# Sheet1.net
KiCad netlist of a schematic drawn in Altium Designer
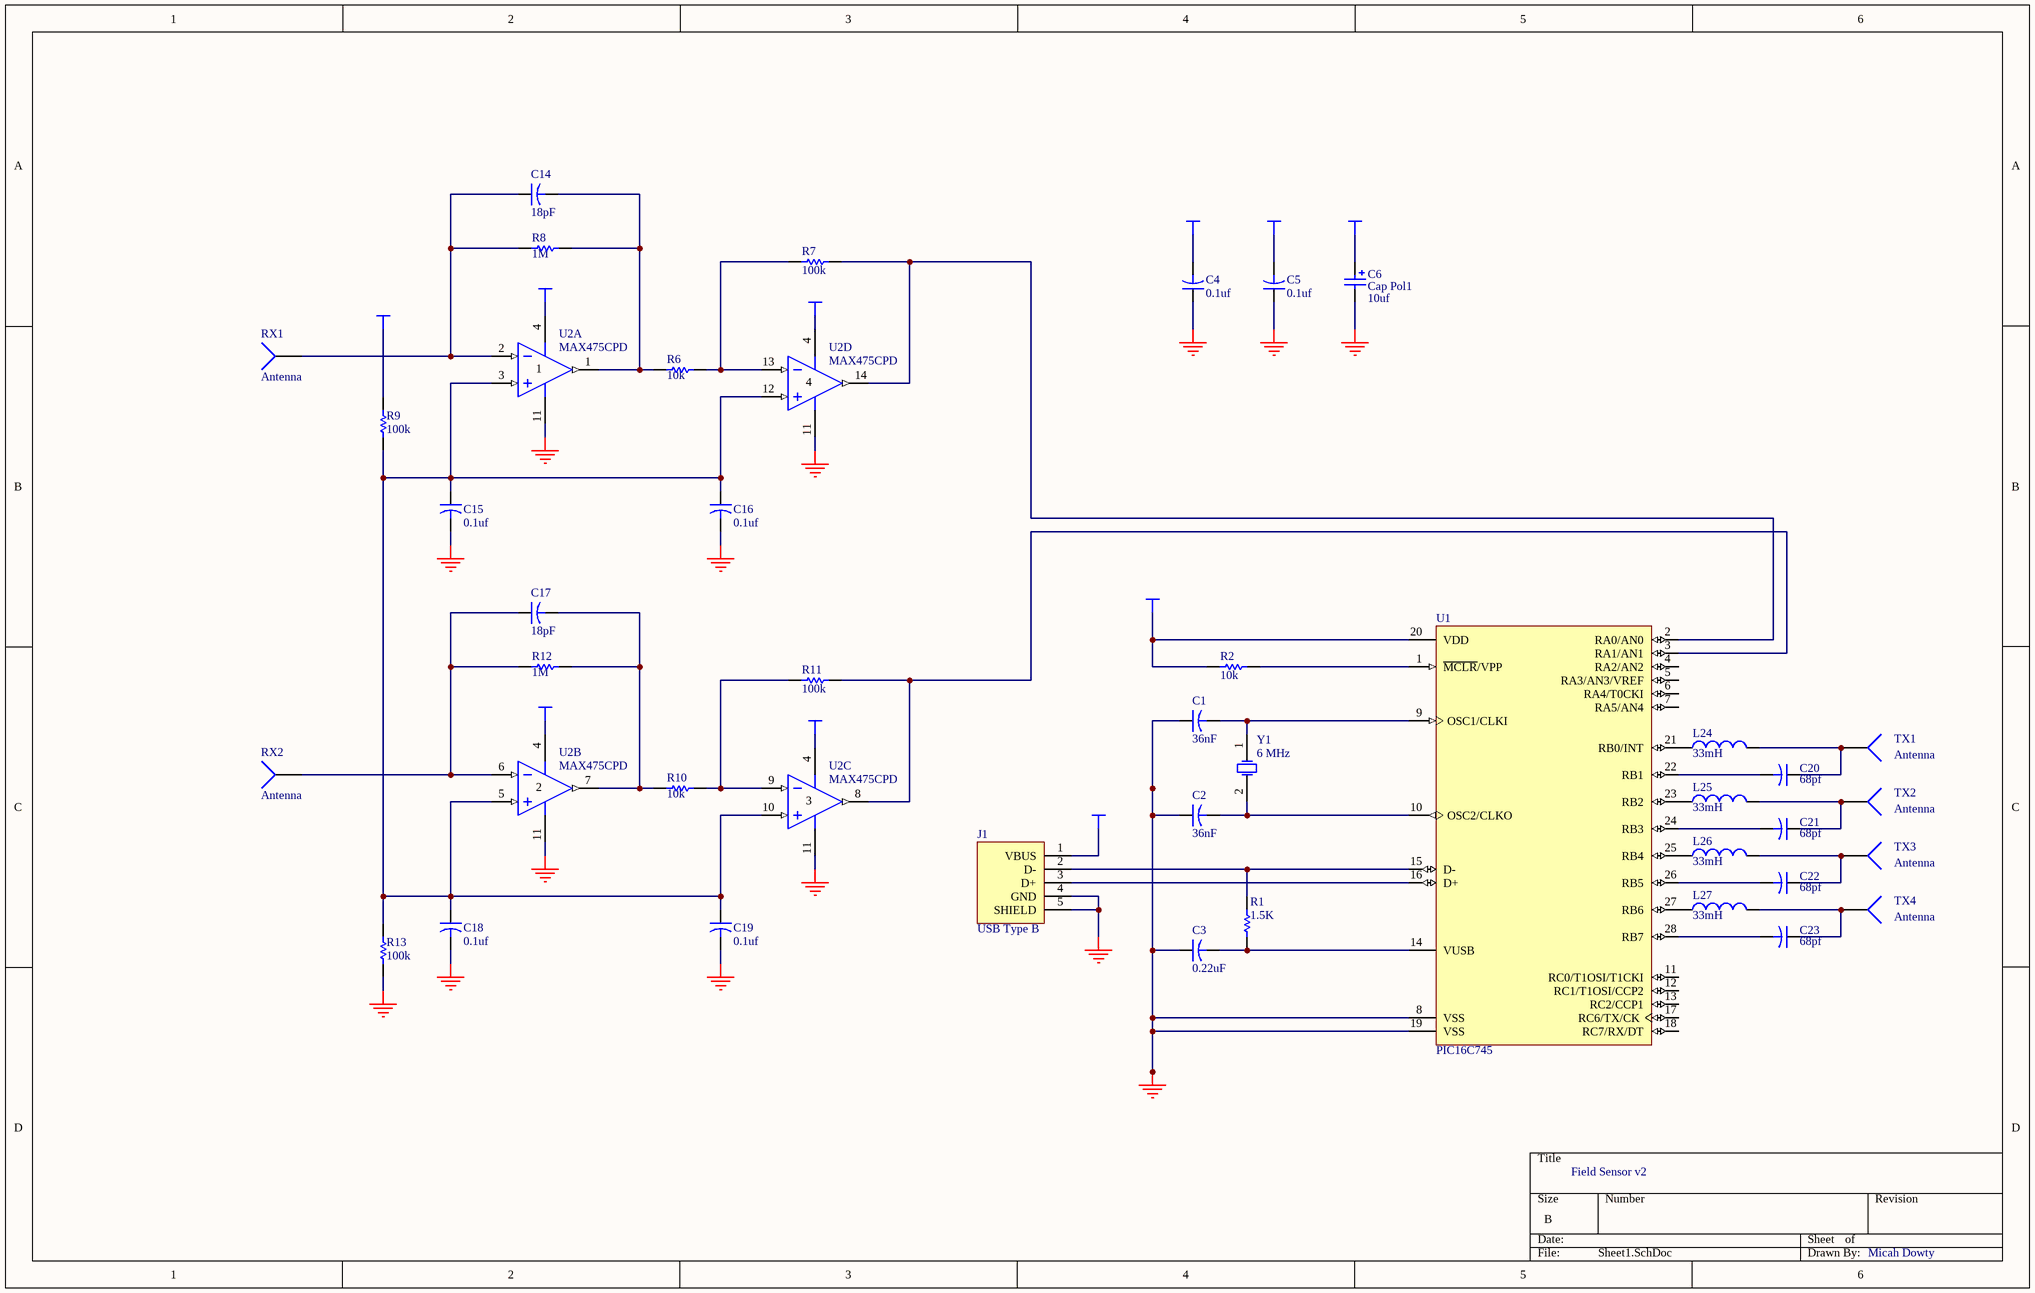
[diagram p0: Sheet1.SchDoc]

(export (version "E")
  (design (tool "Eeschema 10.0.6"))
  (components
    (comp (ref "C1")
      (value "Cap2")
      (footprint "CAPR5-4X5")
      (description "Capacitor")
      (fields
        (field (name "MANUFACTURER") "Generic Components")
        (field (name "ALTIUM_VALUE") "36nF")
        (field (name "PUBLISHER") "Altium Limited")
      )
      (libsource (lib "Miscellaneous Devices") (part "Cap2"))
    )
    (comp (ref "C2")
      (value "Cap2")
      (footprint "CAPR5-4X5")
      (description "Capacitor")
      (fields
        (field (name "MANUFACTURER") "Generic Components")
        (field (name "ALTIUM_VALUE") "36nF")
        (field (name "PUBLISHER") "Altium Limited")
      )
      (libsource (lib "Miscellaneous Devices") (part "Cap2"))
    )
    (comp (ref "C3")
      (value "0.22uF")
      (footprint "CAPR5-4X5")
      (description "Capacitor")
      (fields (field (name "MANUFACTURER") "Generic Components") (field (name "PUBLISHER") "Altium Limited"))
      (libsource (lib "Miscellaneous Devices") (part "Cap2"))
    )
    (comp (ref "C4")
      (value "0.1uf")
      (footprint "CAPR5-4X5")
      (description "Capacitor")
      (fields (field (name "MANUFACTURER") "Generic Components") (field (name "PUBLISHER") "Altium Limited"))
      (libsource (lib "Miscellaneous Devices") (part "Cap2"))
    )
    (comp (ref "C5")
      (value "0.1uf")
      (footprint "CAPR5-4X5")
      (description "Capacitor")
      (fields (field (name "MANUFACTURER") "Generic Components") (field (name "PUBLISHER") "Altium Limited"))
      (libsource (lib "Miscellaneous Devices") (part "Cap2"))
    )
    (comp (ref "C6")
      (value "Cap Pol1")
      (footprint "CAP-EE-1")
      (description "Polarized Capacitor (Radial)")
      (fields
        (field (name "MANUFACTURER") "Generic Components")
        (field (name "ALTIUM_VALUE") "10uf")
        (field (name "PUBLISHER") "Altium Limited")
      )
      (libsource (lib "Miscellaneous Devices") (part "Cap Pol1"))
    )
    (comp (ref "C14")
      (value "Cap2")
      (footprint "CAPR5-4X5")
      (description "Capacitor")
      (fields
        (field (name "MANUFACTURER") "Generic Components")
        (field (name "ALTIUM_VALUE") "18pF")
        (field (name "PUBLISHER") "Altium Limited")
      )
      (libsource (lib "Miscellaneous Devices") (part "Cap2"))
    )
    (comp (ref "C15")
      (value "Cap2")
      (footprint "CAPR5-4X5")
      (description "Capacitor")
      (fields
        (field (name "MANUFACTURER") "Generic Components")
        (field (name "ALTIUM_VALUE") "0.1uf")
        (field (name "PUBLISHER") "Altium Limited")
      )
      (libsource (lib "Miscellaneous Devices") (part "Cap2"))
    )
    (comp (ref "C16")
      (value "Cap2")
      (footprint "CAPR5-4X5")
      (description "Capacitor")
      (fields
        (field (name "MANUFACTURER") "Generic Components")
        (field (name "ALTIUM_VALUE") "0.1uf")
        (field (name "PUBLISHER") "Altium Limited")
      )
      (libsource (lib "Miscellaneous Devices") (part "Cap2"))
    )
    (comp (ref "C17")
      (value "Cap2")
      (footprint "CAPR5-4X5")
      (description "Capacitor")
      (fields
        (field (name "MANUFACTURER") "Generic Components")
        (field (name "ALTIUM_VALUE") "18pF")
        (field (name "PUBLISHER") "Altium Limited")
      )
      (libsource (lib "Miscellaneous Devices") (part "Cap2"))
    )
    (comp (ref "C18")
      (value "Cap2")
      (footprint "CAPR5-4X5")
      (description "Capacitor")
      (fields
        (field (name "MANUFACTURER") "Generic Components")
        (field (name "ALTIUM_VALUE") "0.1uf")
        (field (name "PUBLISHER") "Altium Limited")
      )
      (libsource (lib "Miscellaneous Devices") (part "Cap2"))
    )
    (comp (ref "C19")
      (value "Cap2")
      (footprint "CAPR5-4X5")
      (description "Capacitor")
      (fields
        (field (name "MANUFACTURER") "Generic Components")
        (field (name "ALTIUM_VALUE") "0.1uf")
        (field (name "PUBLISHER") "Altium Limited")
      )
      (libsource (lib "Miscellaneous Devices") (part "Cap2"))
    )
    (comp (ref "C20")
      (value "Cap2")
      (footprint "CAPR5-4X5")
      (description "Capacitor")
      (fields
        (field (name "MANUFACTURER") "Generic Components")
        (field (name "ALTIUM_VALUE") "68pf")
        (field (name "PUBLISHER") "Altium Limited")
      )
      (libsource (lib "Miscellaneous Devices") (part "Cap2"))
    )
    (comp (ref "C21")
      (value "Cap2")
      (footprint "CAPR5-4X5")
      (description "Capacitor")
      (fields
        (field (name "MANUFACTURER") "Generic Components")
        (field (name "ALTIUM_VALUE") "68pf")
        (field (name "PUBLISHER") "Altium Limited")
      )
      (libsource (lib "Miscellaneous Devices") (part "Cap2"))
    )
    (comp (ref "C22")
      (value "Cap2")
      (footprint "CAPR5-4X5")
      (description "Capacitor")
      (fields
        (field (name "MANUFACTURER") "Generic Components")
        (field (name "ALTIUM_VALUE") "68pf")
        (field (name "PUBLISHER") "Altium Limited")
      )
      (libsource (lib "Miscellaneous Devices") (part "Cap2"))
    )
    (comp (ref "C23")
      (value "Cap2")
      (footprint "CAPR5-4X5")
      (description "Capacitor")
      (fields
        (field (name "MANUFACTURER") "Generic Components")
        (field (name "ALTIUM_VALUE") "68pf")
        (field (name "PUBLISHER") "Altium Limited")
      )
      (libsource (lib "Miscellaneous Devices") (part "Cap2"))
    )
    (comp (ref "J1")
      (value "USB")
      (footprint "USB-TYPEB")
      (description "Header, 4-Pin")
      (fields (field (name "MANUFACTURER") "Generic Components") (field (name "PUBLISHER") "Altium Limited"))
      (libsource (lib "parts") (part "USB Type B"))
    )
    (comp (ref "L24")
      (value "33mH")
      (footprint "RAD-0.2")
      (description "Inductor")
      (fields (field (name "MANUFACTURER") "Generic Components") (field (name "PUBLISHER") "Altium Limited"))
      (libsource (lib "Miscellaneous Devices") (part "Inductor"))
    )
    (comp (ref "L25")
      (value "33mH")
      (footprint "RAD-0.2")
      (description "Inductor")
      (fields (field (name "MANUFACTURER") "Generic Components") (field (name "PUBLISHER") "Altium Limited"))
      (libsource (lib "Miscellaneous Devices") (part "Inductor"))
    )
    (comp (ref "L26")
      (value "33mH")
      (footprint "RAD-0.2")
      (description "Inductor")
      (fields (field (name "MANUFACTURER") "Generic Components") (field (name "PUBLISHER") "Altium Limited"))
      (libsource (lib "Miscellaneous Devices") (part "Inductor"))
    )
    (comp (ref "L27")
      (value "33mH")
      (footprint "RAD-0.2")
      (description "Inductor")
      (fields (field (name "MANUFACTURER") "Generic Components") (field (name "PUBLISHER") "Altium Limited"))
      (libsource (lib "Miscellaneous Devices") (part "Inductor"))
    )
    (comp (ref "R1")
      (value "Res1")
      (footprint "AXIAL-0.3")
      (description "Resistor")
      (fields
        (field (name "MANUFACTURER") "Generic Components")
        (field (name "ALTIUM_VALUE") "1.5K")
        (field (name "PUBLISHER") "Altium Limited")
      )
      (libsource (lib "Miscellaneous Devices") (part "Res1"))
    )
    (comp (ref "R2")
      (value "Res1")
      (footprint "AXIAL-0.3")
      (description "Resistor")
      (fields
        (field (name "MANUFACTURER") "Generic Components")
        (field (name "ALTIUM_VALUE") "10k")
        (field (name "PUBLISHER") "Altium Limited")
      )
      (libsource (lib "Miscellaneous Devices") (part "Res1"))
    )
    (comp (ref "R6")
      (value "Res1")
      (footprint "AXIAL-0.3")
      (description "Resistor")
      (fields
        (field (name "MANUFACTURER") "Generic Components")
        (field (name "ALTIUM_VALUE") "10k")
        (field (name "PUBLISHER") "Altium Limited")
      )
      (libsource (lib "Miscellaneous Devices") (part "Res1"))
    )
    (comp (ref "R7")
      (value "Res1")
      (footprint "AXIAL-0.3")
      (description "Resistor")
      (fields
        (field (name "MANUFACTURER") "Generic Components")
        (field (name "ALTIUM_VALUE") "100k")
        (field (name "PUBLISHER") "Altium Limited")
      )
      (libsource (lib "Miscellaneous Devices") (part "Res1"))
    )
    (comp (ref "R8")
      (value "Res1")
      (footprint "AXIAL-0.3")
      (description "Resistor")
      (fields
        (field (name "MANUFACTURER") "Generic Components")
        (field (name "ALTIUM_VALUE") "1M")
        (field (name "PUBLISHER") "Altium Limited")
      )
      (libsource (lib "Miscellaneous Devices") (part "Res1"))
    )
    (comp (ref "R9")
      (value "Res1")
      (footprint "AXIAL-0.3")
      (description "Resistor")
      (fields
        (field (name "MANUFACTURER") "Generic Components")
        (field (name "ALTIUM_VALUE") "100k")
        (field (name "PUBLISHER") "Altium Limited")
      )
      (libsource (lib "Miscellaneous Devices") (part "Res1"))
    )
    (comp (ref "R10")
      (value "Res1")
      (footprint "AXIAL-0.3")
      (description "Resistor")
      (fields
        (field (name "MANUFACTURER") "Generic Components")
        (field (name "ALTIUM_VALUE") "10k")
        (field (name "PUBLISHER") "Altium Limited")
      )
      (libsource (lib "Miscellaneous Devices") (part "Res1"))
    )
    (comp (ref "R11")
      (value "Res1")
      (footprint "AXIAL-0.3")
      (description "Resistor")
      (fields
        (field (name "MANUFACTURER") "Generic Components")
        (field (name "ALTIUM_VALUE") "100k")
        (field (name "PUBLISHER") "Altium Limited")
      )
      (libsource (lib "Miscellaneous Devices") (part "Res1"))
    )
    (comp (ref "R12")
      (value "Res1")
      (footprint "AXIAL-0.3")
      (description "Resistor")
      (fields
        (field (name "MANUFACTURER") "Generic Components")
        (field (name "ALTIUM_VALUE") "1M")
        (field (name "PUBLISHER") "Altium Limited")
      )
      (libsource (lib "Miscellaneous Devices") (part "Res1"))
    )
    (comp (ref "R13")
      (value "Res1")
      (footprint "AXIAL-0.3")
      (description "Resistor")
      (fields
        (field (name "MANUFACTURER") "Generic Components")
        (field (name "ALTIUM_VALUE") "100k")
        (field (name "PUBLISHER") "Altium Limited")
      )
      (libsource (lib "Miscellaneous Devices") (part "Res1"))
    )
    (comp (ref "RX1")
      (value "Antenna")
      (footprint "FIELD_ANTENNA")
      (description "Socket")
      (fields (field (name "MANUFACTURER") "Generic Components") (field (name "PUBLISHER") "Altium Limited"))
      (libsource (lib "Miscellaneous Connectors") (part "Socket"))
    )
    (comp (ref "RX2")
      (value "Antenna")
      (footprint "FIELD_ANTENNA")
      (description "Socket")
      (fields (field (name "MANUFACTURER") "Generic Components") (field (name "PUBLISHER") "Altium Limited"))
      (libsource (lib "Miscellaneous Connectors") (part "Socket"))
    )
    (comp (ref "TX1")
      (value "Antenna")
      (footprint "FIELD_ANTENNA")
      (description "Socket")
      (fields (field (name "MANUFACTURER") "Generic Components") (field (name "PUBLISHER") "Altium Limited"))
      (libsource (lib "Miscellaneous Connectors") (part "Socket"))
    )
    (comp (ref "TX2")
      (value "Antenna")
      (footprint "FIELD_ANTENNA")
      (description "Socket")
      (fields (field (name "MANUFACTURER") "Generic Components") (field (name "PUBLISHER") "Altium Limited"))
      (libsource (lib "Miscellaneous Connectors") (part "Socket"))
    )
    (comp (ref "TX3")
      (value "Antenna")
      (footprint "FIELD_ANTENNA")
      (description "Socket")
      (fields (field (name "MANUFACTURER") "Generic Components") (field (name "PUBLISHER") "Altium Limited"))
      (libsource (lib "Miscellaneous Connectors") (part "Socket"))
    )
    (comp (ref "TX4")
      (value "Antenna")
      (footprint "FIELD_ANTENNA")
      (description "Socket")
      (fields (field (name "MANUFACTURER") "Generic Components") (field (name "PUBLISHER") "Altium Limited"))
      (libsource (lib "Miscellaneous Connectors") (part "Socket"))
    )
    (comp (ref "U1")
      (value "~")
      (footprint "DIP-28")
      (description "EPROM-Based 8-Bit CMOS Microcontroller with USB")
      (fields (field (name "MANUFACTURER") "Microchip"))
      (libsource (lib "parts") (part "PIC16C745"))
    )
    (comp (ref "U2")
      (value "MAX475CPD")
      (footprint "DIP-14/D19.7")
      (description "Quad 10MHz, Single Supply Operational Amplifier")
      (fields (field (name "MANUFACTURER") "Maxim") (field (name "PUBLISHER") "Altium Limited"))
      (libsource (lib "Maxim Operational Amplifier") (part "MAX475CPD"))
    )
    (comp (ref "Y1")
      (value "6 MHz")
      (footprint "BCY-W2/E4.7")
      (description "Crystal Oscillator")
      (fields (field (name "MANUFACTURER") "Generic Components") (field (name "PUBLISHER") "Altium Limited"))
      (libsource (lib "Miscellaneous Devices") (part "XTAL"))
    )
  )
  (nets
    (net (code "1") (name "GND") (class "Default")
      (node (ref "C1") (pin "1") (pinfunction "1_1") (pintype "passive"))
      (node (ref "C15") (pin "2") (pinfunction "2_2") (pintype "passive"))
      (node (ref "C16") (pin "2") (pinfunction "2_2") (pintype "passive"))
      (node (ref "C18") (pin "2") (pinfunction "2_2") (pintype "passive"))
      (node (ref "C19") (pin "2") (pinfunction "2_2") (pintype "passive"))
      (node (ref "C2") (pin "1") (pinfunction "1_1") (pintype "passive"))
      (node (ref "C3") (pin "1") (pinfunction "1_1") (pintype "passive"))
      (node (ref "C4") (pin "1") (pinfunction "1_1") (pintype "passive"))
      (node (ref "C5") (pin "1") (pinfunction "1_1") (pintype "passive"))
      (node (ref "C6") (pin "2") (pinfunction "2_2") (pintype "passive"))
      (node (ref "J1") (pin "4") (pinfunction "GND_4") (pintype "passive"))
      (node (ref "J1") (pin "5") (pinfunction "SHIELD_5") (pintype "power_in"))
      (node (ref "R13") (pin "1") (pinfunction "1_1") (pintype "passive"))
      (node (ref "U1") (pin "19") (pinfunction "VSS_19") (pintype "power_in"))
      (node (ref "U1") (pin "8") (pinfunction "VSS_8") (pintype "power_in"))
      (node (ref "U2") (pin "11") (pinfunction "VEE_11") (pintype "power_in"))
    )
    (net (code "2") (name "Net-(C20-Pad1)") (class "Default")
      (node (ref "C20") (pin "1") (pinfunction "1_1") (pintype "passive"))
      (node (ref "L24") (pin "2") (pinfunction "2_2") (pintype "passive"))
      (node (ref "TX1") (pin "1") (pinfunction "1_1") (pintype "passive"))
    )
    (net (code "3") (name "Net-(C21-Pad1)") (class "Default")
      (node (ref "C21") (pin "1") (pinfunction "1_1") (pintype "passive"))
      (node (ref "L25") (pin "2") (pinfunction "2_2") (pintype "passive"))
      (node (ref "TX2") (pin "1") (pinfunction "1_1") (pintype "passive"))
    )
    (net (code "4") (name "Net-(C22-Pad1)") (class "Default")
      (node (ref "C22") (pin "1") (pinfunction "1_1") (pintype "passive"))
      (node (ref "L26") (pin "2") (pinfunction "2_2") (pintype "passive"))
      (node (ref "TX3") (pin "1") (pinfunction "1_1") (pintype "passive"))
    )
    (net (code "5") (name "Net-(C23-Pad1)") (class "Default")
      (node (ref "C23") (pin "1") (pinfunction "1_1") (pintype "passive"))
      (node (ref "L27") (pin "2") (pinfunction "2_2") (pintype "passive"))
      (node (ref "TX4") (pin "1") (pinfunction "1_1") (pintype "passive"))
    )
    (net (code "6") (name "Net-(J1-D+)") (class "Default")
      (node (ref "J1") (pin "3") (pinfunction "D+_3") (pintype "passive"))
      (node (ref "U1") (pin "16") (pinfunction "D+_16") (pintype "bidirectional"))
    )
    (net (code "7") (name "Net-(J1-D-)") (class "Default")
      (node (ref "J1") (pin "2") (pinfunction "D-_2") (pintype "passive"))
      (node (ref "R1") (pin "2") (pinfunction "2_2") (pintype "passive"))
      (node (ref "U1") (pin "15") (pinfunction "D-_15") (pintype "bidirectional"))
    )
    (net (code "8") (name "Net-(U1-OSC1{slash}CLKI)") (class "Default")
      (node (ref "C1") (pin "2") (pinfunction "2_2") (pintype "passive"))
      (node (ref "U1") (pin "9") (pinfunction "OSC1/CLKI_9") (pintype "input"))
      (node (ref "Y1") (pin "1") (pinfunction "OSC1_1") (pintype "passive"))
    )
    (net (code "9") (name "Net-(U1-OSC2{slash}CLKO)") (class "Default")
      (node (ref "C2") (pin "2") (pinfunction "2_2") (pintype "passive"))
      (node (ref "U1") (pin "10") (pinfunction "OSC2/CLKO_10") (pintype "output"))
      (node (ref "Y1") (pin "2") (pinfunction "OSC2_2") (pintype "passive"))
    )
    (net (code "10") (name "Net-(U1-RA0{slash}AN0)") (class "Default")
      (node (ref "R7") (pin "2") (pinfunction "2_2") (pintype "passive"))
      (node (ref "U1") (pin "2") (pinfunction "RA0/AN0_2") (pintype "bidirectional"))
      (node (ref "U2") (pin "14") (pinfunction "OUT_14") (pintype "output"))
    )
    (net (code "11") (name "Net-(U1-RA1{slash}AN1)") (class "Default")
      (node (ref "R11") (pin "2") (pinfunction "2_2") (pintype "passive"))
      (node (ref "U1") (pin "3") (pinfunction "RA1/AN1_3") (pintype "bidirectional"))
      (node (ref "U2") (pin "8") (pinfunction "OUT_8") (pintype "output"))
    )
    (net (code "12") (name "Net-(U1-RB0{slash}INT)") (class "Default")
      (node (ref "L24") (pin "1") (pinfunction "1_1") (pintype "passive"))
      (node (ref "U1") (pin "21") (pinfunction "RB0/INT_21") (pintype "bidirectional"))
    )
    (net (code "13") (name "Net-(U1-RB1)") (class "Default")
      (node (ref "C20") (pin "2") (pinfunction "2_2") (pintype "passive"))
      (node (ref "U1") (pin "22") (pinfunction "RB1_22") (pintype "bidirectional"))
    )
    (net (code "14") (name "Net-(U1-RB2)") (class "Default")
      (node (ref "L25") (pin "1") (pinfunction "1_1") (pintype "passive"))
      (node (ref "U1") (pin "23") (pinfunction "RB2_23") (pintype "bidirectional"))
    )
    (net (code "15") (name "Net-(U1-RB3)") (class "Default")
      (node (ref "C21") (pin "2") (pinfunction "2_2") (pintype "passive"))
      (node (ref "U1") (pin "24") (pinfunction "RB3_24") (pintype "bidirectional"))
    )
    (net (code "16") (name "Net-(U1-RB4)") (class "Default")
      (node (ref "L26") (pin "1") (pinfunction "1_1") (pintype "passive"))
      (node (ref "U1") (pin "25") (pinfunction "RB4_25") (pintype "bidirectional"))
    )
    (net (code "17") (name "Net-(U1-RB5)") (class "Default")
      (node (ref "C22") (pin "2") (pinfunction "2_2") (pintype "passive"))
      (node (ref "U1") (pin "26") (pinfunction "RB5_26") (pintype "bidirectional"))
    )
    (net (code "18") (name "Net-(U1-RB6)") (class "Default")
      (node (ref "L27") (pin "1") (pinfunction "1_1") (pintype "passive"))
      (node (ref "U1") (pin "27") (pinfunction "RB6_27") (pintype "bidirectional"))
    )
    (net (code "19") (name "Net-(U1-RB7)") (class "Default")
      (node (ref "C23") (pin "2") (pinfunction "2_2") (pintype "passive"))
      (node (ref "U1") (pin "28") (pinfunction "RB7_28") (pintype "bidirectional"))
    )
    (net (code "20") (name "Net-(U1-VUSB)") (class "Default")
      (node (ref "C3") (pin "2") (pinfunction "2_2") (pintype "passive"))
      (node (ref "R1") (pin "1") (pinfunction "1_1") (pintype "passive"))
      (node (ref "U1") (pin "14") (pinfunction "VUSB_14") (pintype "power_in"))
    )
    (net (code "21") (name "Net-(U1-~{MCLR}{slash}VPP)") (class "Default")
      (node (ref "R2") (pin "1") (pinfunction "1_1") (pintype "passive"))
      (node (ref "U1") (pin "1") (pinfunction "~{MCLR}/VPP_1") (pintype "input"))
    )
    (net (code "22") (name "Net-(U2A-IN+)") (class "Default")
      (node (ref "C15") (pin "1") (pinfunction "1_1") (pintype "passive"))
      (node (ref "C16") (pin "1") (pinfunction "1_1") (pintype "passive"))
      (node (ref "C18") (pin "1") (pinfunction "1_1") (pintype "passive"))
      (node (ref "C19") (pin "1") (pinfunction "1_1") (pintype "passive"))
      (node (ref "R13") (pin "2") (pinfunction "2_2") (pintype "passive"))
      (node (ref "R9") (pin "1") (pinfunction "1_1") (pintype "passive"))
      (node (ref "U2") (pin "10") (pinfunction "IN+_10") (pintype "input"))
      (node (ref "U2") (pin "12") (pinfunction "IN+_12") (pintype "input"))
      (node (ref "U2") (pin "3") (pinfunction "IN+_3") (pintype "input"))
      (node (ref "U2") (pin "5") (pinfunction "IN+_5") (pintype "input"))
    )
    (net (code "23") (name "Net-(U2A-IN-)") (class "Default")
      (node (ref "C14") (pin "1") (pinfunction "1_1") (pintype "passive"))
      (node (ref "R8") (pin "1") (pinfunction "1_1") (pintype "passive"))
      (node (ref "RX1") (pin "1") (pinfunction "1_1") (pintype "passive"))
      (node (ref "U2") (pin "2") (pinfunction "IN-_2") (pintype "input"))
    )
    (net (code "24") (name "Net-(U2A-OUT)") (class "Default")
      (node (ref "C14") (pin "2") (pinfunction "2_2") (pintype "passive"))
      (node (ref "R6") (pin "1") (pinfunction "1_1") (pintype "passive"))
      (node (ref "R8") (pin "2") (pinfunction "2_2") (pintype "passive"))
      (node (ref "U2") (pin "1") (pinfunction "OUT_1") (pintype "output"))
    )
    (net (code "25") (name "Net-(U2B-IN-)") (class "Default")
      (node (ref "C17") (pin "1") (pinfunction "1_1") (pintype "passive"))
      (node (ref "R12") (pin "1") (pinfunction "1_1") (pintype "passive"))
      (node (ref "RX2") (pin "1") (pinfunction "1_1") (pintype "passive"))
      (node (ref "U2") (pin "6") (pinfunction "IN-_6") (pintype "input"))
    )
    (net (code "26") (name "Net-(U2B-OUT)") (class "Default")
      (node (ref "C17") (pin "2") (pinfunction "2_2") (pintype "passive"))
      (node (ref "R10") (pin "1") (pinfunction "1_1") (pintype "passive"))
      (node (ref "R12") (pin "2") (pinfunction "2_2") (pintype "passive"))
      (node (ref "U2") (pin "7") (pinfunction "OUT_7") (pintype "output"))
    )
    (net (code "27") (name "Net-(U2C-IN-)") (class "Default")
      (node (ref "R10") (pin "2") (pinfunction "2_2") (pintype "passive"))
      (node (ref "R11") (pin "1") (pinfunction "1_1") (pintype "passive"))
      (node (ref "U2") (pin "9") (pinfunction "IN-_9") (pintype "input"))
    )
    (net (code "28") (name "Net-(U2D-IN-)") (class "Default")
      (node (ref "R6") (pin "2") (pinfunction "2_2") (pintype "passive"))
      (node (ref "R7") (pin "1") (pinfunction "1_1") (pintype "passive"))
      (node (ref "U2") (pin "13") (pinfunction "IN-_13") (pintype "input"))
    )
    (net (code "29") (name "VCC") (class "Default")
      (node (ref "C4") (pin "2") (pinfunction "2_2") (pintype "passive"))
      (node (ref "C5") (pin "2") (pinfunction "2_2") (pintype "passive"))
      (node (ref "C6") (pin "1") (pinfunction "1_1") (pintype "passive"))
      (node (ref "J1") (pin "1") (pinfunction "VBUS_1") (pintype "passive"))
      (node (ref "R2") (pin "2") (pinfunction "2_2") (pintype "passive"))
      (node (ref "R9") (pin "2") (pinfunction "2_2") (pintype "passive"))
      (node (ref "U1") (pin "20") (pinfunction "VDD_20") (pintype "power_in"))
      (node (ref "U2") (pin "4") (pinfunction "VCC_4") (pintype "power_in"))
    )
    (net (code "30") (name "unconnected-(U1-RA2{slash}AN2-Pad4)") (class "Default")
      (node (ref "U1") (pin "4") (pinfunction "RA2/AN2_4") (pintype "bidirectional"))
    )
    (net (code "31") (name "unconnected-(U1-RA3{slash}AN3{slash}VREF-Pad5)") (class "Default")
      (node (ref "U1") (pin "5") (pinfunction "RA3/AN3/VREF_5") (pintype "bidirectional"))
    )
    (net (code "32") (name "unconnected-(U1-RA4{slash}T0CKI-Pad6)") (class "Default")
      (node (ref "U1") (pin "6") (pinfunction "RA4/T0CKI_6") (pintype "bidirectional"))
    )
    (net (code "33") (name "unconnected-(U1-RA5{slash}AN4-Pad7)") (class "Default")
      (node (ref "U1") (pin "7") (pinfunction "RA5/AN4_7") (pintype "bidirectional"))
    )
    (net (code "34") (name "unconnected-(U1-RC0{slash}T1OSI{slash}T1CKI-Pad11)") (class "Default")
      (node (ref "U1") (pin "11") (pinfunction "RC0/T1OSI/T1CKI_11") (pintype "bidirectional"))
    )
    (net (code "35") (name "unconnected-(U1-RC1{slash}T1OSI{slash}CCP2-Pad12)") (class "Default")
      (node (ref "U1") (pin "12") (pinfunction "RC1/T1OSI/CCP2_12") (pintype "bidirectional"))
    )
    (net (code "36") (name "unconnected-(U1-RC2{slash}CCP1-Pad13)") (class "Default")
      (node (ref "U1") (pin "13") (pinfunction "RC2/CCP1_13") (pintype "bidirectional"))
    )
    (net (code "37") (name "unconnected-(U1-RC6{slash}TX{slash}CK-Pad17)") (class "Default")
      (node (ref "U1") (pin "17") (pinfunction "RC6/TX/CK_17") (pintype "bidirectional"))
    )
    (net (code "38") (name "unconnected-(U1-RC7{slash}RX{slash}DT-Pad18)") (class "Default")
      (node (ref "U1") (pin "18") (pinfunction "RC7/RX/DT_18") (pintype "bidirectional"))
    )
  )
)
